# Sheet1.net
KiCad netlist of a schematic drawn in Altium Designer
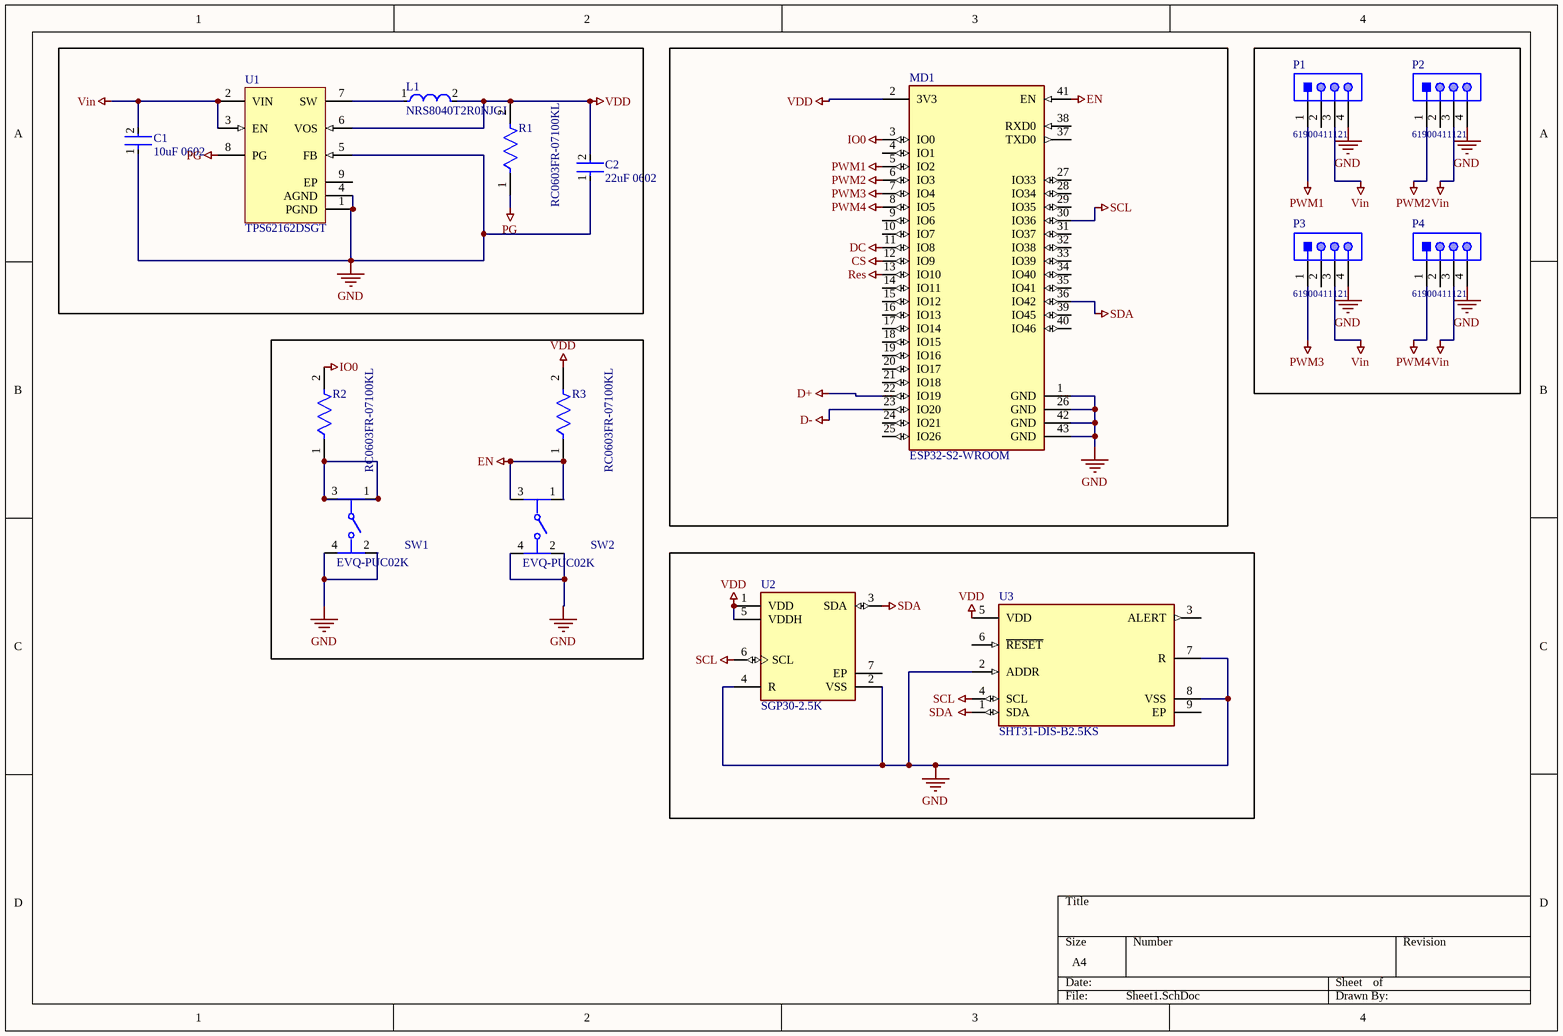
[diagram p0: Sheet1.SchDoc]

(export (version "E")
  (design (tool "Eeschema 10.0.6"))
  (components
    (comp (ref "C1")
      (value "10uF 0602")
      (footprint "FP-GRM188-0_1-e0_2_0_55-IPC_A")
      (description "Chip Multilayer Ceramic Capacitors for General Purpose, 0603, 10uF, X5R, 15%, 20%, 6.3V")
      (fields (field (name "VOLTAGE") "6.3V") (field (name "TOLERANCE") "20%"))
      (libsource (lib "Altium Content Vault") (part "02cd4be3c70576c341d710602a673aa"))
    )
    (comp (ref "C2")
      (value "22uF 0602")
      (footprint "FP-GRM188-0_1-e0_2_0_55-IPC_A")
      (description "Chip Multilayer Ceramic Capacitors for General Purpose, 0603, 10uF, X5R, 15%, 20%, 6.3V")
      (fields (field (name "VOLTAGE") "6.3V") (field (name "TOLERANCE") "20%"))
      (libsource (lib "Altium Content Vault") (part "02cd4be3c70576c341d710602a673aa"))
    )
    (comp (ref "L1")
      (value "NRS8040T2R0NJGJ")
      (footprint "FP-NR8040-H_4_2-MFG")
      (description "Shielded Wirewound Inductor 2uH 30% 7.6A 11.7mΩ SMD")
      (fields (field (name "TOLERANCE") "30%"))
      (libsource (lib "Altium Content Vault") (part "725321dda6339637d4d059423bc1c3c"))
    )
    (comp (ref "MD1")
      (value "ESP32-S2-WROOM")
      (footprint "FP-ESP32-S2-WROOM-MFG")
      (description "RX TXRX MOD WIFI SURFACE MOUNT")
      (libsource (lib "Altium Content Vault") (part "dfe856f8f0070eb901285bddcc8df6c"))
    )
    (comp (ref "P1")
      (value "61900411121")
      (footprint "61900411121")
      (description "Male Locking Header WR-WTB, THT, Vertical, pitch 2.54 mm, 1 x 4 position")
      (fields (field (name "MANUFACTURER") "Wurth Elektronik") (field (name "PUBLISHER") "WurthElektronik"))
      (libsource (lib "Altium Content Vault") (part "WE-CN-1P-M-R4"))
    )
    (comp (ref "P2")
      (value "61900411121")
      (footprint "61900411121")
      (description "Male Locking Header WR-WTB, THT, Vertical, pitch 2.54 mm, 1 x 4 position")
      (fields (field (name "MANUFACTURER") "Wurth Elektronik") (field (name "PUBLISHER") "WurthElektronik"))
      (libsource (lib "Altium Content Vault") (part "WE-CN-1P-M-R4"))
    )
    (comp (ref "P3")
      (value "61900411121")
      (footprint "61900411121")
      (description "Male Locking Header WR-WTB, THT, Vertical, pitch 2.54 mm, 1 x 4 position")
      (fields (field (name "MANUFACTURER") "Wurth Elektronik") (field (name "PUBLISHER") "WurthElektronik"))
      (libsource (lib "Altium Content Vault") (part "WE-CN-1P-M-R4"))
    )
    (comp (ref "P4")
      (value "61900411121")
      (footprint "61900411121")
      (description "Male Locking Header WR-WTB, THT, Vertical, pitch 2.54 mm, 1 x 4 position")
      (fields (field (name "MANUFACTURER") "Wurth Elektronik") (field (name "PUBLISHER") "WurthElektronik"))
      (libsource (lib "Altium Content Vault") (part "WE-CN-1P-M-R4"))
    )
    (comp (ref "R1")
      (value "RC0603FR-07100KL")
      (footprint "FP-RC0603-0_55-MFG")
      (description "RES SMD 100K OHM 1% 1/10W 0603")
      (fields (field (name "TOLERANCE") "1%"))
      (libsource (lib "Altium Content Vault") (part "1029c3af85768c4190bb7ad29bc67b5"))
    )
    (comp (ref "R2")
      (value "RC0603FR-07100KL")
      (footprint "FP-RC0603-0_55-MFG")
      (description "RES SMD 100K OHM 1% 1/10W 0603")
      (fields (field (name "TOLERANCE") "1%"))
      (libsource (lib "Altium Content Vault") (part "1029c3af85768c4190bb7ad29bc67b5"))
    )
    (comp (ref "R3")
      (value "RC0603FR-07100KL")
      (footprint "FP-RC0603-0_55-MFG")
      (description "RES SMD 100K OHM 1% 1/10W 0603")
      (fields (field (name "TOLERANCE") "1%"))
      (libsource (lib "Altium Content Vault") (part "1029c3af85768c4190bb7ad29bc67b5"))
    )
    (comp (ref "SW1")
      (value "EVQ-PUC02K")
      (footprint "FP-EVQ-PUC02K-MFG")
      (description "SWITCH TACTILE SPST-NO 0.05A 12V")
      (libsource (lib "Altium Content Vault") (part "cb67941ecbda1860b707deecc235d4d"))
    )
    (comp (ref "SW2")
      (value "EVQ-PUC02K")
      (footprint "FP-EVQ-PUC02K-MFG")
      (description "SWITCH TACTILE SPST-NO 0.05A 12V")
      (libsource (lib "Altium Content Vault") (part "cb67941ecbda1860b707deecc235d4d"))
    )
    (comp (ref "U1")
      (value "TPS62162DSGT")
      (footprint "DSG0008A_V")
      (fields (field (name "MANUFACTURER") "Texas Instruments"))
      (libsource (lib "Altium Content Vault") (part "TI-TPS62162DSG8-1600X900TP"))
    )
    (comp (ref "U2")
      (value "SGP30-2.5K")
      (footprint "FP-SGP30-2_5K-MFG")
      (description "Air Quality Sensor I²C")
      (fields (field (name "OCTOPART") "https://octopart.com/sgp30-2.5k-sensirion-84561789"))
      (libsource (lib "Altium Content Vault") (part "83c16ec1942eefe8a5a6f6958230d5f"))
    )
    (comp (ref "U3")
      (value "SHT31-DIS-B2.5KS")
      (footprint "FP-SHT31-DIS-B2_5KS-MFG")
      (description "SENSOR HUMID/TEMP 5V I2C 2% SMD")
      (libsource (lib "Altium Content Vault") (part "666307a9354d2867b06523a408f450d"))
    )
  )
  (nets
    (net (code "1") (name "CS") (class "Default")
      (node (ref "MD1") (pin "12") (pinfunction "IO9_12") (pintype "bidirectional"))
    )
    (net (code "2") (name "D+") (class "Default")
      (node (ref "MD1") (pin "22") (pinfunction "IO19_22") (pintype "bidirectional"))
    )
    (net (code "3") (name "D-") (class "Default")
      (node (ref "MD1") (pin "23") (pinfunction "IO20_23") (pintype "bidirectional"))
    )
    (net (code "4") (name "DC") (class "Default")
      (node (ref "MD1") (pin "11") (pinfunction "IO8_11") (pintype "bidirectional"))
    )
    (net (code "5") (name "EN") (class "Default")
      (node (ref "MD1") (pin "41") (pinfunction "EN_41") (pintype "input"))
      (node (ref "R3") (pin "1") (pinfunction "1_1") (pintype "passive"))
      (node (ref "SW2") (pin "1") (pinfunction "1_1") (pintype "passive"))
      (node (ref "SW2") (pin "3") (pinfunction "3_3") (pintype "passive"))
    )
    (net (code "6") (name "GND") (class "Default")
      (node (ref "C1") (pin "1") (pinfunction "1_1") (pintype "passive"))
      (node (ref "C2") (pin "1") (pinfunction "1_1") (pintype "passive"))
      (node (ref "MD1") (pin "1") (pinfunction "GND_1") (pintype "power_in"))
      (node (ref "MD1") (pin "26") (pinfunction "GND_26") (pintype "power_in"))
      (node (ref "MD1") (pin "42") (pinfunction "GND_42") (pintype "power_in"))
      (node (ref "MD1") (pin "43") (pinfunction "GND_43") (pintype "power_in"))
      (node (ref "P1") (pin "4") (pinfunction "4_4") (pintype "passive"))
      (node (ref "P2") (pin "4") (pinfunction "4_4") (pintype "passive"))
      (node (ref "P3") (pin "4") (pinfunction "4_4") (pintype "passive"))
      (node (ref "P4") (pin "4") (pinfunction "4_4") (pintype "passive"))
      (node (ref "SW1") (pin "2") (pinfunction "2_2") (pintype "passive"))
      (node (ref "SW1") (pin "4") (pinfunction "4_4") (pintype "passive"))
      (node (ref "SW2") (pin "2") (pinfunction "2_2") (pintype "passive"))
      (node (ref "SW2") (pin "4") (pinfunction "4_4") (pintype "passive"))
      (node (ref "U1") (pin "1") (pinfunction "PGND_1") (pintype "power_in"))
      (node (ref "U1") (pin "4") (pinfunction "AGND_4") (pintype "power_in"))
      (node (ref "U1") (pin "5") (pinfunction "FB_5") (pintype "input"))
      (node (ref "U2") (pin "2") (pinfunction "VSS_2") (pintype "power_in"))
      (node (ref "U2") (pin "4") (pinfunction "R_4") (pintype "power_in"))
      (node (ref "U3") (pin "2") (pinfunction "ADDR_2") (pintype "input"))
      (node (ref "U3") (pin "7") (pinfunction "R_7") (pintype "passive"))
      (node (ref "U3") (pin "8") (pinfunction "VSS_8") (pintype "power_in"))
    )
    (net (code "7") (name "IO0") (class "Default")
      (node (ref "MD1") (pin "3") (pinfunction "IO0_3") (pintype "bidirectional"))
      (node (ref "R2") (pin "2") (pinfunction "2_2") (pintype "passive"))
    )
    (net (code "8") (name "Net-(R2-Pad1)") (class "Default")
      (node (ref "R2") (pin "1") (pinfunction "1_1") (pintype "passive"))
      (node (ref "SW1") (pin "1") (pinfunction "1_1") (pintype "passive"))
      (node (ref "SW1") (pin "3") (pinfunction "3_3") (pintype "passive"))
    )
    (net (code "9") (name "Net-(U1-SW)") (class "Default")
      (node (ref "L1") (pin "1") (pinfunction "1_1") (pintype "passive"))
      (node (ref "U1") (pin "7") (pinfunction "SW_7") (pintype "power_in"))
    )
    (net (code "10") (name "PG") (class "Default")
      (node (ref "R1") (pin "1") (pinfunction "1_1") (pintype "passive"))
      (node (ref "U1") (pin "8") (pinfunction "PG_8") (pintype "tri_state"))
    )
    (net (code "11") (name "PWM1") (class "Default")
      (node (ref "MD1") (pin "5") (pinfunction "IO2_5") (pintype "bidirectional"))
      (node (ref "P1") (pin "1") (pinfunction "1_1") (pintype "passive"))
    )
    (net (code "12") (name "PWM2") (class "Default")
      (node (ref "MD1") (pin "6") (pinfunction "IO3_6") (pintype "bidirectional"))
      (node (ref "P2") (pin "1") (pinfunction "1_1") (pintype "passive"))
    )
    (net (code "13") (name "PWM3") (class "Default")
      (node (ref "MD1") (pin "7") (pinfunction "IO4_7") (pintype "bidirectional"))
      (node (ref "P3") (pin "1") (pinfunction "1_1") (pintype "passive"))
    )
    (net (code "14") (name "PWM4") (class "Default")
      (node (ref "MD1") (pin "8") (pinfunction "IO5_8") (pintype "bidirectional"))
      (node (ref "P4") (pin "1") (pinfunction "1_1") (pintype "passive"))
    )
    (net (code "15") (name "Res") (class "Default")
      (node (ref "MD1") (pin "13") (pinfunction "IO10_13") (pintype "bidirectional"))
    )
    (net (code "16") (name "SCL") (class "Default")
      (node (ref "MD1") (pin "30") (pinfunction "IO36_30") (pintype "bidirectional"))
      (node (ref "U2") (pin "6") (pinfunction "SCL_6") (pintype "bidirectional"))
      (node (ref "U3") (pin "4") (pinfunction "SCL_4") (pintype "bidirectional"))
    )
    (net (code "17") (name "SDA") (class "Default")
      (node (ref "MD1") (pin "36") (pinfunction "IO42_36") (pintype "bidirectional"))
      (node (ref "U2") (pin "3") (pinfunction "SDA_3") (pintype "bidirectional"))
      (node (ref "U3") (pin "1") (pinfunction "SDA_1") (pintype "bidirectional"))
    )
    (net (code "18") (name "VDD") (class "Default")
      (node (ref "C2") (pin "2") (pinfunction "2_2") (pintype "passive"))
      (node (ref "L1") (pin "2") (pinfunction "2_2") (pintype "passive"))
      (node (ref "MD1") (pin "2") (pinfunction "3V3_2") (pintype "power_in"))
      (node (ref "R1") (pin "2") (pinfunction "2_2") (pintype "passive"))
      (node (ref "R3") (pin "2") (pinfunction "2_2") (pintype "passive"))
      (node (ref "U1") (pin "6") (pinfunction "VOS_6") (pintype "input"))
      (node (ref "U2") (pin "1") (pinfunction "VDD_1") (pintype "power_in"))
      (node (ref "U2") (pin "5") (pinfunction "VDDH_5") (pintype "power_in"))
      (node (ref "U3") (pin "5") (pinfunction "VDD_5") (pintype "power_in"))
    )
    (net (code "19") (name "Vin") (class "Default")
      (node (ref "C1") (pin "2") (pinfunction "2_2") (pintype "passive"))
      (node (ref "P1") (pin "3") (pinfunction "3_3") (pintype "passive"))
      (node (ref "P2") (pin "3") (pinfunction "3_3") (pintype "passive"))
      (node (ref "P3") (pin "3") (pinfunction "3_3") (pintype "passive"))
      (node (ref "P4") (pin "3") (pinfunction "3_3") (pintype "passive"))
      (node (ref "U1") (pin "2") (pinfunction "VIN_2") (pintype "power_in"))
      (node (ref "U1") (pin "3") (pinfunction "EN_3") (pintype "input"))
    )
    (net (code "20") (name "unconnected-(MD1-IO1-Pad4)") (class "Default")
      (node (ref "MD1") (pin "4") (pinfunction "IO1_4") (pintype "bidirectional"))
    )
    (net (code "21") (name "unconnected-(MD1-IO6-Pad9)") (class "Default")
      (node (ref "MD1") (pin "9") (pinfunction "IO6_9") (pintype "bidirectional"))
    )
    (net (code "22") (name "unconnected-(MD1-IO7-Pad10)") (class "Default")
      (node (ref "MD1") (pin "10") (pinfunction "IO7_10") (pintype "bidirectional"))
    )
    (net (code "23") (name "unconnected-(MD1-IO11-Pad14)") (class "Default")
      (node (ref "MD1") (pin "14") (pinfunction "IO11_14") (pintype "bidirectional"))
    )
    (net (code "24") (name "unconnected-(MD1-IO12-Pad15)") (class "Default")
      (node (ref "MD1") (pin "15") (pinfunction "IO12_15") (pintype "bidirectional"))
    )
    (net (code "25") (name "unconnected-(MD1-IO13-Pad16)") (class "Default")
      (node (ref "MD1") (pin "16") (pinfunction "IO13_16") (pintype "bidirectional"))
    )
    (net (code "26") (name "unconnected-(MD1-IO14-Pad17)") (class "Default")
      (node (ref "MD1") (pin "17") (pinfunction "IO14_17") (pintype "bidirectional"))
    )
    (net (code "27") (name "unconnected-(MD1-IO15-Pad18)") (class "Default")
      (node (ref "MD1") (pin "18") (pinfunction "IO15_18") (pintype "bidirectional"))
    )
    (net (code "28") (name "unconnected-(MD1-IO16-Pad19)") (class "Default")
      (node (ref "MD1") (pin "19") (pinfunction "IO16_19") (pintype "bidirectional"))
    )
    (net (code "29") (name "unconnected-(MD1-IO17-Pad20)") (class "Default")
      (node (ref "MD1") (pin "20") (pinfunction "IO17_20") (pintype "bidirectional"))
    )
    (net (code "30") (name "unconnected-(MD1-IO18-Pad21)") (class "Default")
      (node (ref "MD1") (pin "21") (pinfunction "IO18_21") (pintype "bidirectional"))
    )
    (net (code "31") (name "unconnected-(MD1-IO21-Pad24)") (class "Default")
      (node (ref "MD1") (pin "24") (pinfunction "IO21_24") (pintype "bidirectional"))
    )
    (net (code "32") (name "unconnected-(MD1-IO26-Pad25)") (class "Default")
      (node (ref "MD1") (pin "25") (pinfunction "IO26_25") (pintype "bidirectional"))
    )
    (net (code "33") (name "unconnected-(MD1-IO33-Pad27)") (class "Default")
      (node (ref "MD1") (pin "27") (pinfunction "IO33_27") (pintype "bidirectional"))
    )
    (net (code "34") (name "unconnected-(MD1-IO34-Pad28)") (class "Default")
      (node (ref "MD1") (pin "28") (pinfunction "IO34_28") (pintype "bidirectional"))
    )
    (net (code "35") (name "unconnected-(MD1-IO35-Pad29)") (class "Default")
      (node (ref "MD1") (pin "29") (pinfunction "IO35_29") (pintype "bidirectional"))
    )
    (net (code "36") (name "unconnected-(MD1-IO37-Pad31)") (class "Default")
      (node (ref "MD1") (pin "31") (pinfunction "IO37_31") (pintype "bidirectional"))
    )
    (net (code "37") (name "unconnected-(MD1-IO38-Pad32)") (class "Default")
      (node (ref "MD1") (pin "32") (pinfunction "IO38_32") (pintype "bidirectional"))
    )
    (net (code "38") (name "unconnected-(MD1-IO39-Pad33)") (class "Default")
      (node (ref "MD1") (pin "33") (pinfunction "IO39_33") (pintype "bidirectional"))
    )
    (net (code "39") (name "unconnected-(MD1-IO40-Pad34)") (class "Default")
      (node (ref "MD1") (pin "34") (pinfunction "IO40_34") (pintype "bidirectional"))
    )
    (net (code "40") (name "unconnected-(MD1-IO41-Pad35)") (class "Default")
      (node (ref "MD1") (pin "35") (pinfunction "IO41_35") (pintype "bidirectional"))
    )
    (net (code "41") (name "unconnected-(MD1-IO45-Pad39)") (class "Default")
      (node (ref "MD1") (pin "39") (pinfunction "IO45_39") (pintype "bidirectional"))
    )
    (net (code "42") (name "unconnected-(MD1-IO46-Pad40)") (class "Default")
      (node (ref "MD1") (pin "40") (pinfunction "IO46_40") (pintype "bidirectional"))
    )
    (net (code "43") (name "unconnected-(MD1-RXD0-Pad38)") (class "Default")
      (node (ref "MD1") (pin "38") (pinfunction "RXD0_38") (pintype "input"))
    )
    (net (code "44") (name "unconnected-(MD1-TXD0-Pad37)") (class "Default")
      (node (ref "MD1") (pin "37") (pinfunction "TXD0_37") (pintype "output"))
    )
    (net (code "45") (name "unconnected-(P1-Pad2)") (class "Default")
      (node (ref "P1") (pin "2") (pinfunction "2_2") (pintype "passive"))
    )
    (net (code "46") (name "unconnected-(P2-Pad2)") (class "Default")
      (node (ref "P2") (pin "2") (pinfunction "2_2") (pintype "passive"))
    )
    (net (code "47") (name "unconnected-(P3-Pad2)") (class "Default")
      (node (ref "P3") (pin "2") (pinfunction "2_2") (pintype "passive"))
    )
    (net (code "48") (name "unconnected-(P4-Pad2)") (class "Default")
      (node (ref "P4") (pin "2") (pinfunction "2_2") (pintype "passive"))
    )
    (net (code "49") (name "unconnected-(U1-EP-Pad9)") (class "Default")
      (node (ref "U1") (pin "9") (pinfunction "EP_9") (pintype "power_in"))
    )
    (net (code "50") (name "unconnected-(U2-EP-Pad7)") (class "Default")
      (node (ref "U2") (pin "7") (pinfunction "EP_7") (pintype "passive"))
    )
    (net (code "51") (name "unconnected-(U3-ALERT-Pad3)") (class "Default")
      (node (ref "U3") (pin "3") (pinfunction "ALERT_3") (pintype "output"))
    )
    (net (code "52") (name "unconnected-(U3-EP-Pad9)") (class "Default")
      (node (ref "U3") (pin "9") (pinfunction "EP_9") (pintype "power_in"))
    )
    (net (code "53") (name "unconnected-(U3-~{RESET}-Pad6)") (class "Default")
      (node (ref "U3") (pin "6") (pinfunction "~{RESET}_6") (pintype "input"))
    )
  )
)
